# 4_11.net
KiCad netlist of a schematic drawn in EasyEDA
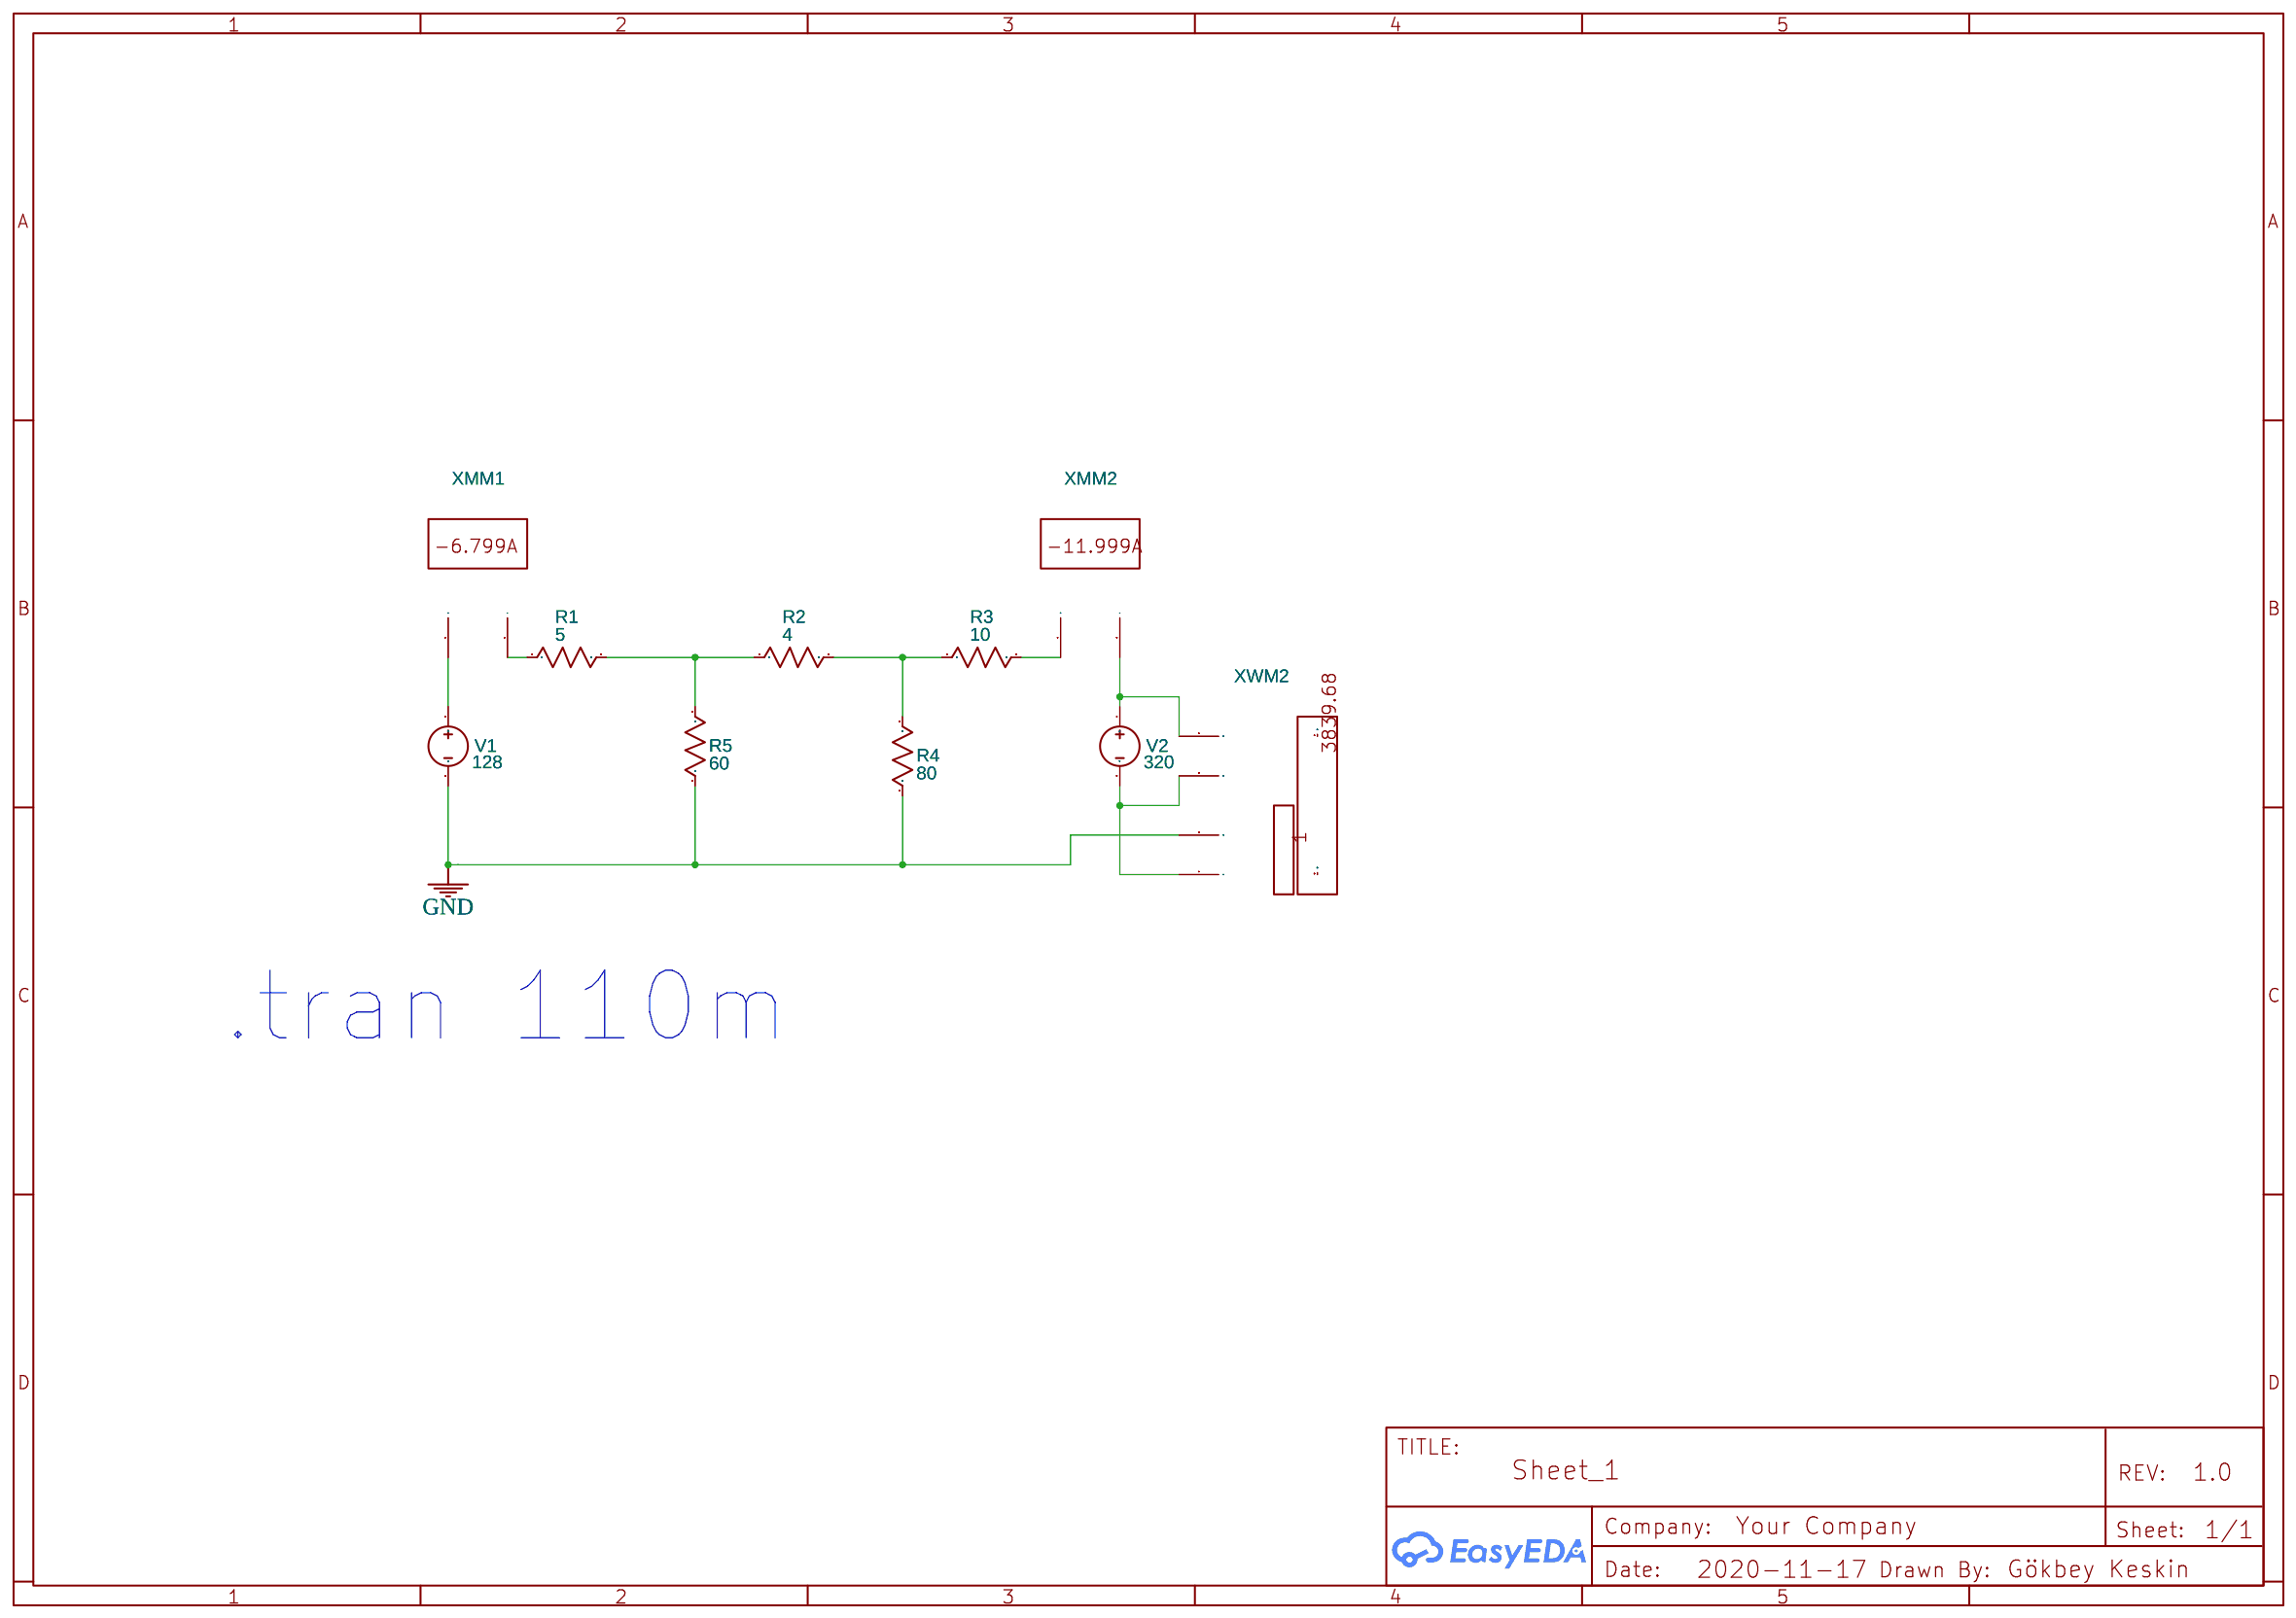
[diagram p0: schematic sheet]

(export (version "E")
  (design (tool "Eeschema 10.0.6"))
  (components
    (comp (ref "R1") (value "5") (libsource (lib "") (part "Resistor_US_1")))
    (comp (ref "R2") (value "4") (libsource (lib "") (part "Resistor_US_1")))
    (comp (ref "R3") (value "10") (libsource (lib "") (part "Resistor_US_1")))
    (comp (ref "R4") (value "80") (libsource (lib "") (part "Resistor_US")))
    (comp (ref "R5") (value "60") (libsource (lib "") (part "Resistor_US")))
    (comp (ref "V1") (value "128") (libsource (lib "") (part "VDC")))
    (comp (ref "V2") (value "320") (libsource (lib "") (part "VDC")))
    (comp (ref "XMM1") (value "Multimeter") (libsource (lib "") (part "MULTIMETER")))
    (comp (ref "XMM2") (value "Multimeter") (libsource (lib "") (part "MULTIMETER_1")))
    (comp (ref "XWM2") (value "Wattmeter") (libsource (lib "") (part "WATTMETER")))
  )
  (nets
    (net (code "1") (name "GND") (class "Default")
      (node (ref "R4") (pin "1") (pinfunction "1_1") (pintype "unspecified"))
      (node (ref "R5") (pin "1") (pinfunction "1_1") (pintype "unspecified"))
      (node (ref "V1") (pin "2") (pinfunction "2_2") (pintype "unspecified"))
      (node (ref "XWM2") (pin "3") (pinfunction "I+_3") (pintype "unspecified"))
    )
    (net (code "2") (name "Net-(R1-Pad2)") (class "Default")
      (node (ref "R1") (pin "2") (pinfunction "2_2") (pintype "unspecified"))
      (node (ref "R2") (pin "1") (pinfunction "1_1") (pintype "unspecified"))
      (node (ref "R5") (pin "2") (pinfunction "2_2") (pintype "unspecified"))
    )
    (net (code "3") (name "Net-(R2-Pad2)") (class "Default")
      (node (ref "R2") (pin "2") (pinfunction "2_2") (pintype "unspecified"))
      (node (ref "R3") (pin "1") (pinfunction "1_1") (pintype "unspecified"))
      (node (ref "R4") (pin "2") (pinfunction "2_2") (pintype "unspecified"))
    )
    (net (code "4") (name "Net-(XMM1-+)") (class "Default")
      (node (ref "V1") (pin "1") (pinfunction "1_1") (pintype "unspecified"))
      (node (ref "XMM1") (pin "1") (pinfunction "+_1") (pintype "unspecified"))
    )
    (net (code "5") (name "Net-(XMM1-I)") (class "Default")
      (node (ref "R1") (pin "1") (pinfunction "1_1") (pintype "unspecified"))
      (node (ref "XMM1") (pin "2") (pinfunction "I_2") (pintype "unspecified"))
    )
    (net (code "6") (name "Net-(XMM2-+)") (class "Default")
      (node (ref "R3") (pin "2") (pinfunction "2_2") (pintype "unspecified"))
      (node (ref "XMM2") (pin "1") (pinfunction "+_1") (pintype "unspecified"))
    )
    (net (code "7") (name "Net-(XMM2-I)") (class "Default")
      (node (ref "V2") (pin "1") (pinfunction "1_1") (pintype "unspecified"))
      (node (ref "XMM2") (pin "2") (pinfunction "I_2") (pintype "unspecified"))
      (node (ref "XWM2") (pin "1") (pinfunction "V+_1") (pintype "unspecified"))
    )
    (net (code "8") (name "Net-(XWM2-I-)") (class "Default")
      (node (ref "V2") (pin "2") (pinfunction "2_2") (pintype "unspecified"))
      (node (ref "XWM2") (pin "2") (pinfunction "V-_2") (pintype "unspecified"))
      (node (ref "XWM2") (pin "4") (pinfunction "I-_4") (pintype "unspecified"))
    )
    (net (code "9") (name "unconnected-(XWM2-PadP)") (class "Default")
      (node (ref "XWM2") (pin "P") (pinfunction "P_P") (pintype "unspecified"))
    )
    (net (code "10") (name "unconnected-(XWM2-PadPF)") (class "Default")
      (node (ref "XWM2") (pin "PF") (pinfunction "PF_PF") (pintype "unspecified"))
    )
  )
)
